# Impedance_R6_Updated.net
KiCad netlist of a schematic drawn in EAGLE
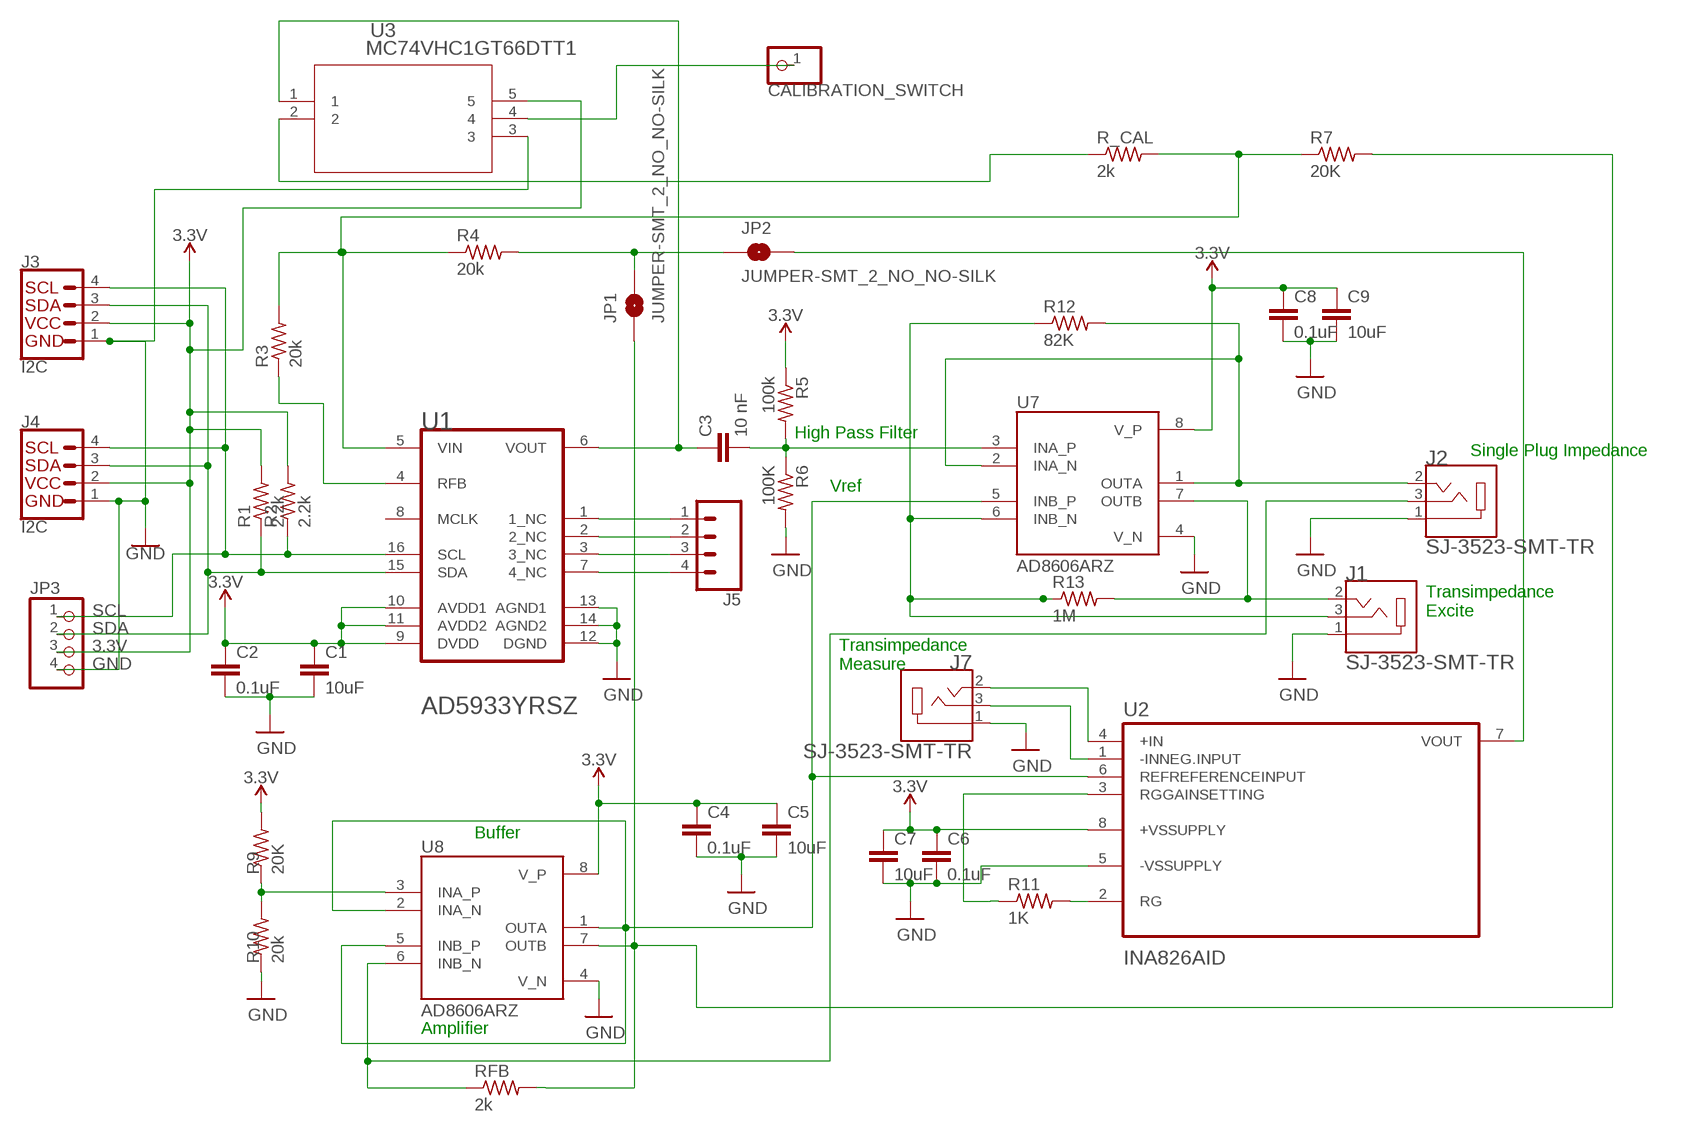
[diagram p0: schematic, sheet 1]

(export (version "E")
  (design (tool "Eeschema 10.0.6"))
  (components
    (comp (ref "C1")
      (value "10uF")
      (footprint "eagle-import:C0603")
      (libsource (lib "eagle-import") (part "C-EUC0603"))
    )
    (comp (ref "C2")
      (value "0.1uF")
      (footprint "eagle-import:C0603")
      (libsource (lib "eagle-import") (part "C-EUC0603"))
    )
    (comp (ref "C3")
      (value "10 nF")
      (footprint "eagle-import:C0603")
      (libsource (lib "eagle-import") (part "C-EUC0603"))
    )
    (comp (ref "C4")
      (value "0.1uF")
      (footprint "eagle-import:C0603")
      (libsource (lib "eagle-import") (part "C-EUC0603"))
    )
    (comp (ref "C5")
      (value "10uF")
      (footprint "eagle-import:C0603")
      (libsource (lib "eagle-import") (part "C-EUC0603"))
    )
    (comp (ref "C6")
      (value "0.1uF")
      (footprint "eagle-import:C0603")
      (libsource (lib "eagle-import") (part "C-EUC0603"))
    )
    (comp (ref "C7")
      (value "10uF")
      (footprint "eagle-import:C0603")
      (libsource (lib "eagle-import") (part "C-EUC0603"))
    )
    (comp (ref "C8")
      (value "0.1uF")
      (footprint "eagle-import:C0603")
      (libsource (lib "eagle-import") (part "C-EUC0603"))
    )
    (comp (ref "C9")
      (value "10uF")
      (footprint "eagle-import:C0603")
      (libsource (lib "eagle-import") (part "C-EUC0603"))
    )
    (comp (ref "CALIBRATION_SWITCH")
      (value "PINHD-1X1")
      (footprint "eagle-import:1X01")
      (libsource (lib "eagle-import") (part "PINHD-1X1"))
    )
    (comp (ref "J1")
      (value "SJ-3523-SMT-TR")
      (footprint "eagle-import:CUI_SJ-3523-SMT-TR")
      (fields (field (name "MF") "CUI Devices"))
      (libsource (lib "eagle-import") (part "SJ-3523-SMT-TR"))
    )
    (comp (ref "J2")
      (value "SJ-3523-SMT-TR")
      (footprint "eagle-import:CUI_SJ-3523-SMT-TR")
      (fields (field (name "MF") "CUI Devices"))
      (libsource (lib "eagle-import") (part "SJ-3523-SMT-TR"))
    )
    (comp (ref "J3")
      (value "I2C")
      (footprint "eagle-import:JST04_1MM_RA")
      (libsource (lib "eagle-import") (part "QWIIC_CONNECTORJS-1MM"))
    )
    (comp (ref "J4")
      (value "I2C")
      (footprint "eagle-import:JST04_1MM_RA")
      (libsource (lib "eagle-import") (part "QWIIC_CONNECTORJS-1MM"))
    )
    (comp (ref "J5")
      (value "CONN_04")
      (footprint "eagle-import:1X04")
      (libsource (lib "eagle-import") (part "CONN_04"))
    )
    (comp (ref "J7")
      (value "SJ-3523-SMT-TR")
      (footprint "eagle-import:CUI_SJ-3523-SMT-TR")
      (fields (field (name "MF") "CUI Devices"))
      (libsource (lib "eagle-import") (part "SJ-3523-SMT-TR"))
    )
    (comp (ref "JP1")
      (value "JUMPER-SMT_2_NO_NO-SILK")
      (footprint "eagle-import:SMT-JUMPER_2_NO_NO-SILK")
      (libsource (lib "eagle-import") (part "JUMPER-SMT_2_NO_NO-SILK"))
    )
    (comp (ref "JP2")
      (value "JUMPER-SMT_2_NO_NO-SILK")
      (footprint "eagle-import:SMT-JUMPER_2_NO_NO-SILK")
      (libsource (lib "eagle-import") (part "JUMPER-SMT_2_NO_NO-SILK"))
    )
    (comp (ref "JP3")
      (value "PINHD-1X4")
      (footprint "eagle-import:1X04")
      (libsource (lib "eagle-import") (part "PINHD-1X4"))
    )
    (comp (ref "R1")
      (value "2.2k")
      (footprint "eagle-import:R0603")
      (libsource (lib "eagle-import") (part "R-US_R0603"))
    )
    (comp (ref "R2")
      (value "2.2k")
      (footprint "eagle-import:R0603")
      (libsource (lib "eagle-import") (part "R-US_R0603"))
    )
    (comp (ref "R3")
      (value "20k")
      (footprint "eagle-import:R0603")
      (libsource (lib "eagle-import") (part "R-US_R0603"))
    )
    (comp (ref "R4")
      (value "20k")
      (footprint "eagle-import:R0603")
      (libsource (lib "eagle-import") (part "R-US_R0603"))
    )
    (comp (ref "R5")
      (value "100k")
      (footprint "eagle-import:R0603")
      (libsource (lib "eagle-import") (part "R-US_R0603"))
    )
    (comp (ref "R6")
      (value "100K")
      (footprint "eagle-import:R0603")
      (libsource (lib "eagle-import") (part "R-US_R0603"))
    )
    (comp (ref "R7")
      (value "20K")
      (footprint "eagle-import:R0603")
      (libsource (lib "eagle-import") (part "R-US_R0603"))
    )
    (comp (ref "R9")
      (value "20K")
      (footprint "eagle-import:R0603")
      (libsource (lib "eagle-import") (part "R-US_R0603"))
    )
    (comp (ref "R10")
      (value "20k")
      (footprint "eagle-import:R0603")
      (libsource (lib "eagle-import") (part "R-US_R0603"))
    )
    (comp (ref "R11")
      (value "1K")
      (footprint "eagle-import:R0603")
      (libsource (lib "eagle-import") (part "R-US_R0603"))
    )
    (comp (ref "R12")
      (value "82K")
      (footprint "eagle-import:R0603")
      (libsource (lib "eagle-import") (part "R-US_R0603"))
    )
    (comp (ref "R13")
      (value "1M")
      (footprint "eagle-import:R0603")
      (libsource (lib "eagle-import") (part "R-US_R0603"))
    )
    (comp (ref "RFB")
      (value "2k")
      (footprint "eagle-import:R0603")
      (libsource (lib "eagle-import") (part "R-US_R0603"))
    )
    (comp (ref "R_CAL")
      (value "2k")
      (footprint "eagle-import:R0603")
      (libsource (lib "eagle-import") (part "R-US_R0603"))
    )
    (comp (ref "U1")
      (value "ANALOG_DEVICES_AD5933YRSZANALOG_DEVICES_AD5933YRSZ_0_0")
      (footprint "eagle-import:ANALOG_DEVICES_AD5933YRSZ_0")
      (fields (field (name "MF") "Analog Devices") (field (name "MPN") "AD5933YRSZ"))
      (libsource (lib "eagle-import") (part "ANALOG_DEVICES_AD5933YRSZANALOG_DEVICES_AD5933YRSZ_0_0"))
    )
    (comp (ref "U2")
      (value "INA826AID")
      (footprint "eagle-import:SOIC127P599X175-8N")
      (fields (field (name "MF") "Texas Instruments"))
      (libsource (lib "eagle-import") (part "INA826AID"))
    )
    (comp (ref "U3")
      (value "MC74VHC1GT66DTT1")
      (footprint "eagle-import:TSOP5_1P65X3P15_ONS")
      (fields (field (name "COPYRIGHT") "Copyright (C) 2024 Ultra Librarian. All rights reserved."))
      (libsource (lib "eagle-import") (part "MC74VHC1GT66DTT1"))
    )
    (comp (ref "U7")
      (value "AD8606ARZ")
      (footprint "eagle-import:SOIC127P600X175-8N")
      (fields (field (name "MF") "Analog Devices"))
      (libsource (lib "eagle-import") (part "AD8606ARZ"))
    )
    (comp (ref "U8")
      (value "AD8606ARZ")
      (footprint "eagle-import:SOIC127P600X175-8N")
      (fields (field (name "MF") "Analog Devices"))
      (libsource (lib "eagle-import") (part "AD8606ARZ"))
    )
  )
  (nets
    (net (code "1") (name "/SCL") (class "Default")
      (node (ref "J3") (pin "4") (pinfunction "4_4") (pintype "passive"))
      (node (ref "J4") (pin "4") (pinfunction "4_4") (pintype "passive"))
      (node (ref "JP3") (pin "1") (pinfunction "1_1") (pintype "passive"))
      (node (ref "R2") (pin "1") (pinfunction "1_1") (pintype "passive"))
      (node (ref "U1") (pin "16") (pinfunction "SCL_16") (pintype "input"))
    )
    (net (code "2") (name "/SDA") (class "Default")
      (node (ref "J3") (pin "3") (pinfunction "3_3") (pintype "passive"))
      (node (ref "J4") (pin "3") (pinfunction "3_3") (pintype "passive"))
      (node (ref "JP3") (pin "2") (pinfunction "2_2") (pintype "passive"))
      (node (ref "R1") (pin "1") (pinfunction "1_1") (pintype "passive"))
      (node (ref "U1") (pin "15") (pinfunction "SDA_15") (pintype "bidirectional"))
    )
    (net (code "3") (name "3.3V") (class "Default")
      (node (ref "C1") (pin "1") (pinfunction "1_1") (pintype "passive"))
      (node (ref "C2") (pin "1") (pinfunction "1_1") (pintype "passive"))
      (node (ref "C4") (pin "1") (pinfunction "1_1") (pintype "passive"))
      (node (ref "C5") (pin "1") (pinfunction "1_1") (pintype "passive"))
      (node (ref "C6") (pin "1") (pinfunction "1_1") (pintype "passive"))
      (node (ref "C7") (pin "1") (pinfunction "1_1") (pintype "passive"))
      (node (ref "C8") (pin "1") (pinfunction "1_1") (pintype "passive"))
      (node (ref "C9") (pin "1") (pinfunction "1_1") (pintype "passive"))
      (node (ref "J3") (pin "2") (pinfunction "2_2") (pintype "power_in"))
      (node (ref "J4") (pin "2") (pinfunction "2_2") (pintype "power_in"))
      (node (ref "JP3") (pin "3") (pinfunction "3_3") (pintype "passive"))
      (node (ref "R1") (pin "2") (pinfunction "2_2") (pintype "passive"))
      (node (ref "R2") (pin "2") (pinfunction "2_2") (pintype "passive"))
      (node (ref "R5") (pin "1") (pinfunction "1_1") (pintype "passive"))
      (node (ref "R9") (pin "2") (pinfunction "2_2") (pintype "passive"))
      (node (ref "U1") (pin "10") (pinfunction "AVDD1_10") (pintype "power_in"))
      (node (ref "U1") (pin "11") (pinfunction "AVDD2_11") (pintype "power_in"))
      (node (ref "U1") (pin "9") (pinfunction "DVDD_9") (pintype "power_in"))
      (node (ref "U2") (pin "8") (pinfunction "+VSSUPPLY_8") (pintype "bidirectional"))
      (node (ref "U3") (pin "5") (pinfunction "5_5") (pintype "passive"))
      (node (ref "U7") (pin "8") (pinfunction "V_P_8") (pintype "power_in"))
      (node (ref "U8") (pin "8") (pinfunction "V_P_8") (pintype "power_in"))
    )
    (net (code "4") (name "GND") (class "Default")
      (node (ref "C1") (pin "2") (pinfunction "2_2") (pintype "passive"))
      (node (ref "C2") (pin "2") (pinfunction "2_2") (pintype "passive"))
      (node (ref "C4") (pin "2") (pinfunction "2_2") (pintype "passive"))
      (node (ref "C5") (pin "2") (pinfunction "2_2") (pintype "passive"))
      (node (ref "C6") (pin "2") (pinfunction "2_2") (pintype "passive"))
      (node (ref "C7") (pin "2") (pinfunction "2_2") (pintype "passive"))
      (node (ref "C8") (pin "2") (pinfunction "2_2") (pintype "passive"))
      (node (ref "C9") (pin "2") (pinfunction "2_2") (pintype "passive"))
      (node (ref "J1") (pin "1") (pinfunction "1_1") (pintype "passive"))
      (node (ref "J2") (pin "1") (pinfunction "1_1") (pintype "passive"))
      (node (ref "J3") (pin "1") (pinfunction "1_1") (pintype "power_in"))
      (node (ref "J4") (pin "1") (pinfunction "1_1") (pintype "power_in"))
      (node (ref "J7") (pin "1") (pinfunction "1_1") (pintype "passive"))
      (node (ref "JP3") (pin "4") (pinfunction "4_4") (pintype "passive"))
      (node (ref "R10") (pin "1") (pinfunction "1_1") (pintype "passive"))
      (node (ref "R6") (pin "2") (pinfunction "2_2") (pintype "passive"))
      (node (ref "U1") (pin "12") (pinfunction "DGND_12") (pintype "power_in"))
      (node (ref "U1") (pin "13") (pinfunction "AGND1_13") (pintype "power_in"))
      (node (ref "U1") (pin "14") (pinfunction "AGND2_14") (pintype "power_in"))
      (node (ref "U2") (pin "5") (pinfunction "-VSSUPPLY_5") (pintype "bidirectional"))
      (node (ref "U3") (pin "3") (pinfunction "3_3") (pintype "passive"))
      (node (ref "U7") (pin "4") (pinfunction "V_N_4") (pintype "power_in"))
      (node (ref "U8") (pin "4") (pinfunction "V_N_4") (pintype "power_in"))
    )
    (net (code "5") (name "Net-(CALIBRATION_SWITCH-Pad1)") (class "Default")
      (node (ref "CALIBRATION_SWITCH") (pin "1") (pinfunction "1_1") (pintype "passive"))
      (node (ref "U3") (pin "4") (pinfunction "4_4") (pintype "passive"))
    )
    (net (code "6") (name "Net-(JP1-Pad2)") (class "Default")
      (node (ref "JP1") (pin "2") (pinfunction "2_2") (pintype "passive"))
      (node (ref "JP2") (pin "1") (pinfunction "1_1") (pintype "passive"))
      (node (ref "R4") (pin "2") (pinfunction "2_2") (pintype "passive"))
    )
    (net (code "7") (name "Net-(R_CAL-Pad1)") (class "Default")
      (node (ref "R_CAL") (pin "1") (pinfunction "1_1") (pintype "passive"))
      (node (ref "U3") (pin "2") (pinfunction "2_2") (pintype "passive"))
    )
    (net (code "8") (name "Net-(U1-1_NC)") (class "Default")
      (node (ref "J5") (pin "1") (pinfunction "1_1") (pintype "passive"))
      (node (ref "U1") (pin "1") (pinfunction "1_NC_1") (pintype "passive"))
    )
    (net (code "9") (name "Net-(U1-2_NC)") (class "Default")
      (node (ref "J5") (pin "2") (pinfunction "2_2") (pintype "passive"))
      (node (ref "U1") (pin "2") (pinfunction "2_NC_2") (pintype "passive"))
    )
    (net (code "10") (name "Net-(U1-3_NC)") (class "Default")
      (node (ref "J5") (pin "3") (pinfunction "3_3") (pintype "passive"))
      (node (ref "U1") (pin "3") (pinfunction "3_NC_3") (pintype "passive"))
    )
    (net (code "11") (name "Net-(U1-4_NC)") (class "Default")
      (node (ref "J5") (pin "4") (pinfunction "4_4") (pintype "passive"))
      (node (ref "U1") (pin "7") (pinfunction "4_NC_7") (pintype "passive"))
    )
    (net (code "12") (name "Net-(U1-RFB)") (class "Default")
      (node (ref "R3") (pin "1") (pinfunction "1_1") (pintype "passive"))
      (node (ref "U1") (pin "4") (pinfunction "RFB_4") (pintype "input"))
    )
    (net (code "13") (name "Net-(U1-VIN)") (class "Default")
      (node (ref "R3") (pin "2") (pinfunction "2_2") (pintype "passive"))
      (node (ref "R4") (pin "1") (pinfunction "1_1") (pintype "passive"))
      (node (ref "R7") (pin "1") (pinfunction "1_1") (pintype "passive"))
      (node (ref "R_CAL") (pin "2") (pinfunction "2_2") (pintype "passive"))
      (node (ref "U1") (pin "5") (pinfunction "VIN_5") (pintype "input"))
    )
    (net (code "14") (name "Net-(U1-VOUT)") (class "Default")
      (node (ref "C3") (pin "1") (pinfunction "1_1") (pintype "passive"))
      (node (ref "U1") (pin "6") (pinfunction "VOUT_6") (pintype "output"))
      (node (ref "U3") (pin "1") (pinfunction "1_1") (pintype "passive"))
    )
    (net (code "15") (name "Net-(U2-+IN)") (class "Default")
      (node (ref "J7") (pin "2") (pinfunction "2_2") (pintype "passive"))
      (node (ref "U2") (pin "4") (pinfunction "+IN_4") (pintype "input"))
    )
    (net (code "16") (name "Net-(U2--INNEG.INPUT)") (class "Default")
      (node (ref "J7") (pin "3") (pinfunction "3_3") (pintype "passive"))
      (node (ref "U2") (pin "1") (pinfunction "-INNEG.INPUT_1") (pintype "input"))
    )
    (net (code "17") (name "Net-(U2-REFREFERENCEINPUT)") (class "Default")
      (node (ref "U2") (pin "6") (pinfunction "REFREFERENCEINPUT_6") (pintype "input"))
      (node (ref "U7") (pin "5") (pinfunction "INB_P_5") (pintype "input"))
      (node (ref "U8") (pin "1") (pinfunction "OUTA_1") (pintype "input"))
      (node (ref "U8") (pin "2") (pinfunction "INA_N_2") (pintype "input"))
      (node (ref "U8") (pin "5") (pinfunction "INB_P_5") (pintype "input"))
    )
    (net (code "18") (name "Net-(U2-RG)") (class "Default")
      (node (ref "R11") (pin "2") (pinfunction "2_2") (pintype "passive"))
      (node (ref "U2") (pin "2") (pinfunction "RG_2") (pintype "bidirectional"))
    )
    (net (code "19") (name "Net-(U2-RGGAINSETTING)") (class "Default")
      (node (ref "R11") (pin "1") (pinfunction "1_1") (pintype "passive"))
      (node (ref "U2") (pin "3") (pinfunction "RGGAINSETTING_3") (pintype "input"))
    )
    (net (code "20") (name "Net-(U2-VOUT)") (class "Default")
      (node (ref "JP2") (pin "2") (pinfunction "2_2") (pintype "passive"))
      (node (ref "U2") (pin "7") (pinfunction "VOUT_7") (pintype "output"))
    )
    (net (code "21") (name "Net-(U7-INA_N)") (class "Default")
      (node (ref "J2") (pin "2") (pinfunction "2_2") (pintype "passive"))
      (node (ref "R12") (pin "2") (pinfunction "2_2") (pintype "passive"))
      (node (ref "U7") (pin "1") (pinfunction "OUTA_1") (pintype "input"))
      (node (ref "U7") (pin "2") (pinfunction "INA_N_2") (pintype "input"))
    )
    (net (code "22") (name "Net-(U7-INA_P)") (class "Default")
      (node (ref "C3") (pin "2") (pinfunction "2_2") (pintype "passive"))
      (node (ref "R5") (pin "2") (pinfunction "2_2") (pintype "passive"))
      (node (ref "R6") (pin "1") (pinfunction "1_1") (pintype "passive"))
      (node (ref "U7") (pin "3") (pinfunction "INA_P_3") (pintype "input"))
    )
    (net (code "23") (name "Net-(U7-INB_N)") (class "Default")
      (node (ref "J1") (pin "3") (pinfunction "3_3") (pintype "passive"))
      (node (ref "R12") (pin "1") (pinfunction "1_1") (pintype "passive"))
      (node (ref "R13") (pin "1") (pinfunction "1_1") (pintype "passive"))
      (node (ref "U7") (pin "6") (pinfunction "INB_N_6") (pintype "input"))
    )
    (net (code "24") (name "Net-(U7-OUTB)") (class "Default")
      (node (ref "J1") (pin "2") (pinfunction "2_2") (pintype "passive"))
      (node (ref "R13") (pin "2") (pinfunction "2_2") (pintype "passive"))
      (node (ref "U7") (pin "7") (pinfunction "OUTB_7") (pintype "input"))
    )
    (net (code "25") (name "Net-(U8-INA_P)") (class "Default")
      (node (ref "R10") (pin "2") (pinfunction "2_2") (pintype "passive"))
      (node (ref "R9") (pin "1") (pinfunction "1_1") (pintype "passive"))
      (node (ref "U8") (pin "3") (pinfunction "INA_P_3") (pintype "input"))
    )
    (net (code "26") (name "Net-(U8-INB_N)") (class "Default")
      (node (ref "J2") (pin "3") (pinfunction "3_3") (pintype "passive"))
      (node (ref "RFB") (pin "1") (pinfunction "1_1") (pintype "passive"))
      (node (ref "U8") (pin "6") (pinfunction "INB_N_6") (pintype "input"))
    )
    (net (code "27") (name "Net-(U8-OUTB)") (class "Default")
      (node (ref "JP1") (pin "1") (pinfunction "1_1") (pintype "passive"))
      (node (ref "R7") (pin "2") (pinfunction "2_2") (pintype "passive"))
      (node (ref "RFB") (pin "2") (pinfunction "2_2") (pintype "passive"))
      (node (ref "U8") (pin "7") (pinfunction "OUTB_7") (pintype "input"))
    )
    (net (code "28") (name "unconnected-(U1-MCLK-Pad8)") (class "Default")
      (node (ref "U1") (pin "8") (pinfunction "MCLK_8") (pintype "input"))
    )
  )
)
